# LED_PCB_Rev2.net
KiCad netlist of a schematic drawn in EAGLE
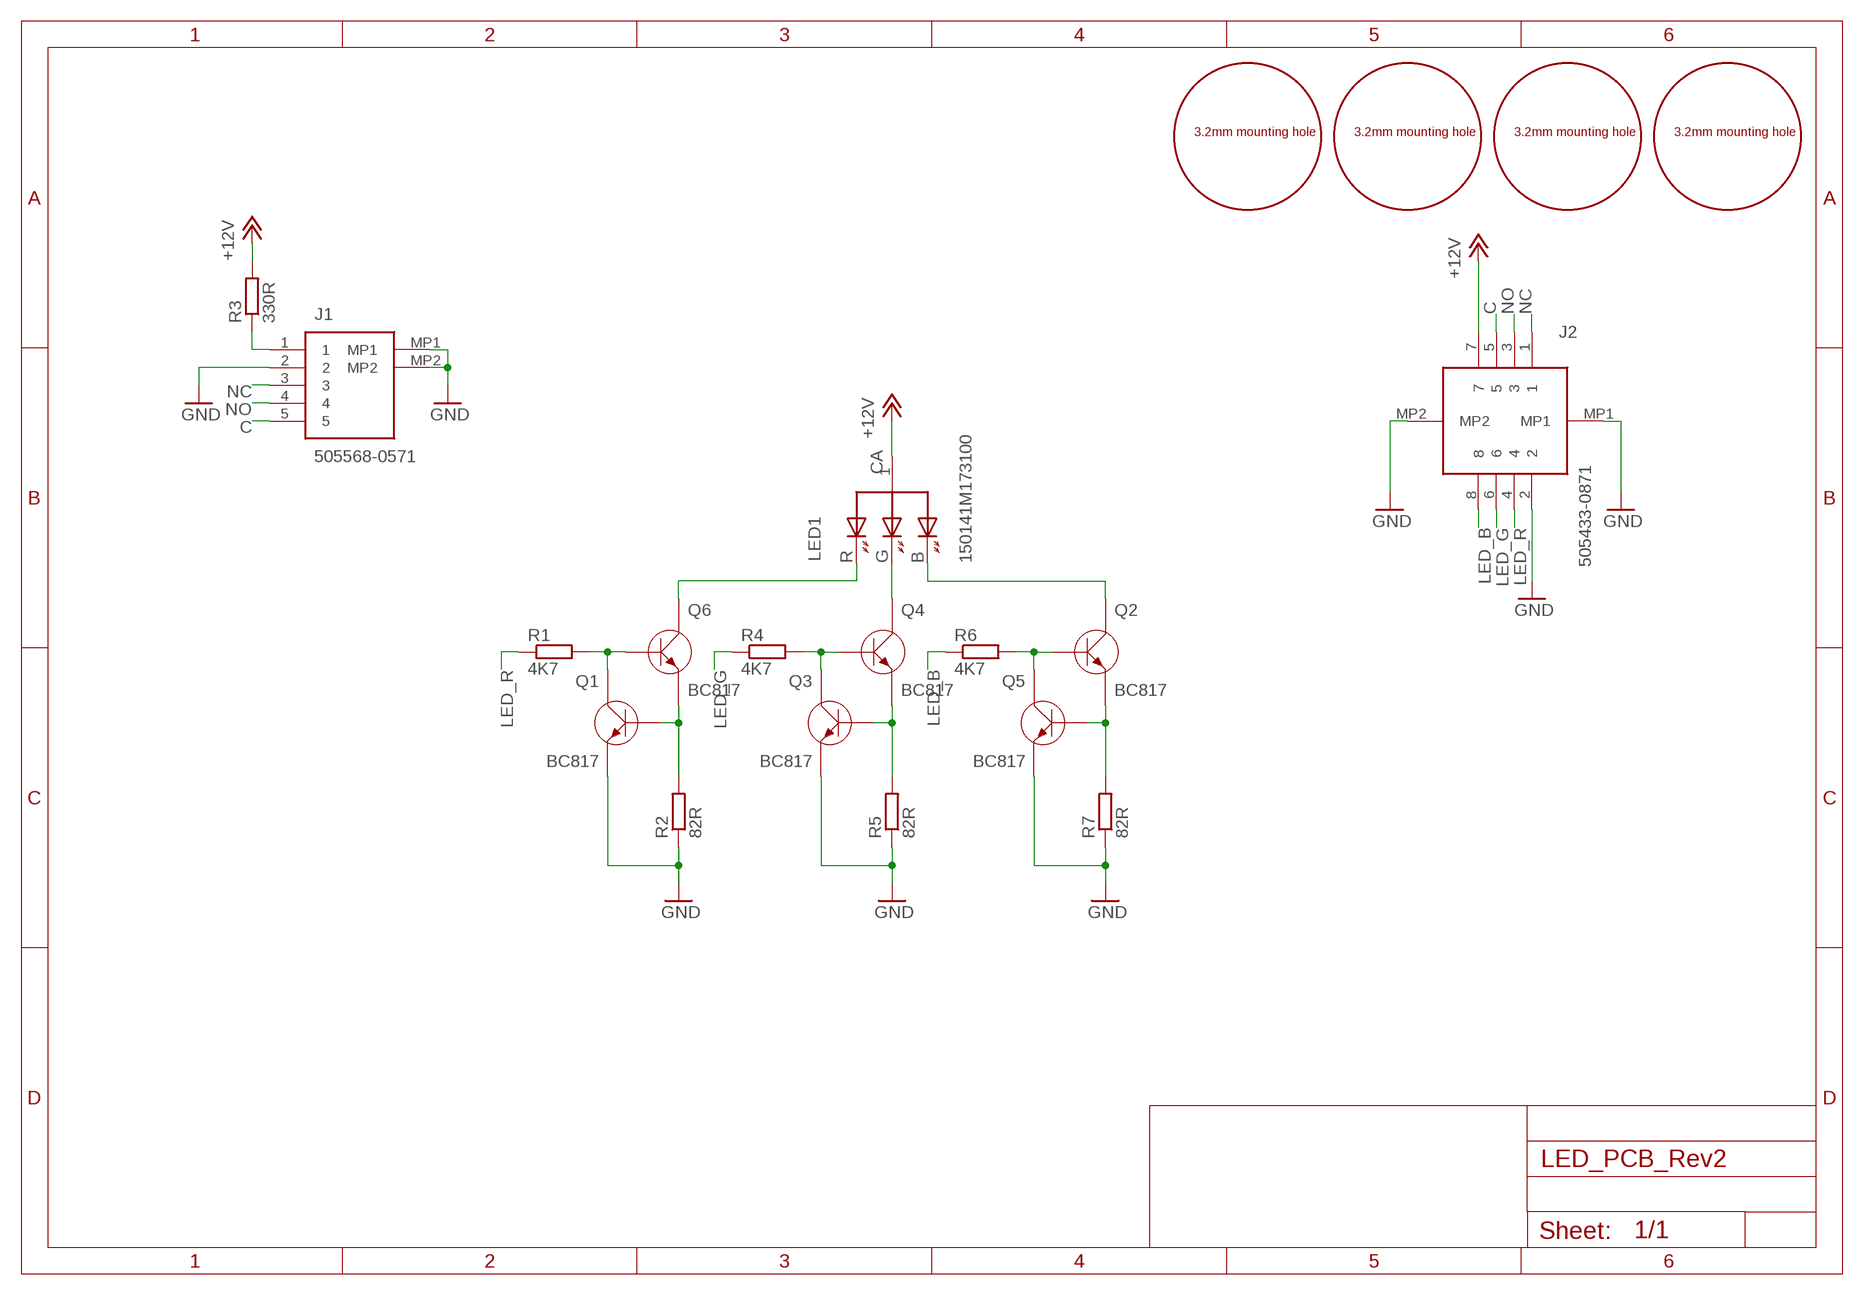
[diagram p0: schematic, sheet 1]

(export (version "E")
  (design (tool "Eeschema 10.0.6"))
  (components
    (comp (ref "J1")
      (value "505568-0571")
      (footprint "eagle-import:5055680571")
      (fields (field (name "RS_PART_NUMBER") "1615926P"))
      (libsource (lib "eagle-import") (part "505568-0571"))
    )
    (comp (ref "J2")
      (value "505433-0871")
      (footprint "eagle-import:5054330871")
      (fields (field (name "MANUFACTURER_PART_NUMBER") "5054330871"))
      (libsource (lib "eagle-import") (part "505433-0871"))
    )
    (comp (ref "LED1")
      (value "150141M173100")
      (footprint "eagle-import:150141M173100")
      (libsource (lib "eagle-import") (part "150141M173100"))
    )
    (comp (ref "Q1")
      (value "BC817")
      (footprint "eagle-import:SOT23")
      (libsource (lib "eagle-import") (part "BC817"))
    )
    (comp (ref "Q2")
      (value "BC817")
      (footprint "eagle-import:SOT23")
      (libsource (lib "eagle-import") (part "BC817"))
    )
    (comp (ref "Q3")
      (value "BC817")
      (footprint "eagle-import:SOT23")
      (libsource (lib "eagle-import") (part "BC817"))
    )
    (comp (ref "Q4")
      (value "BC817")
      (footprint "eagle-import:SOT23")
      (libsource (lib "eagle-import") (part "BC817"))
    )
    (comp (ref "Q5")
      (value "BC817")
      (footprint "eagle-import:SOT23")
      (libsource (lib "eagle-import") (part "BC817"))
    )
    (comp (ref "Q6")
      (value "BC817")
      (footprint "eagle-import:SOT23")
      (libsource (lib "eagle-import") (part "BC817"))
    )
    (comp (ref "R1")
      (value "4K7")
      (footprint "eagle-import:R0603")
      (libsource (lib "eagle-import") (part "R0603"))
    )
    (comp (ref "R2")
      (value "82R")
      (footprint "eagle-import:R0603")
      (libsource (lib "eagle-import") (part "R0603"))
    )
    (comp (ref "R3")
      (value "330R")
      (footprint "eagle-import:R0603")
      (libsource (lib "eagle-import") (part "R0603"))
    )
    (comp (ref "R4")
      (value "4K7")
      (footprint "eagle-import:R0603")
      (libsource (lib "eagle-import") (part "R0603"))
    )
    (comp (ref "R5")
      (value "82R")
      (footprint "eagle-import:R0603")
      (libsource (lib "eagle-import") (part "R0603"))
    )
    (comp (ref "R6")
      (value "4K7")
      (footprint "eagle-import:R0603")
      (libsource (lib "eagle-import") (part "R0603"))
    )
    (comp (ref "R7")
      (value "82R")
      (footprint "eagle-import:R0603")
      (libsource (lib "eagle-import") (part "R0603"))
    )
    (comp (ref "U$1")
      (value "M3_MOUNTING_HOLE")
      (footprint "eagle-import:M3_MOUNTING_HOLE")
      (libsource (lib "eagle-import") (part "M3_MOUNTING_HOLE"))
    )
    (comp (ref "U$2")
      (value "M3_MOUNTING_HOLE")
      (footprint "eagle-import:M3_MOUNTING_HOLE")
      (libsource (lib "eagle-import") (part "M3_MOUNTING_HOLE"))
    )
    (comp (ref "U$3")
      (value "M3_MOUNTING_HOLE")
      (footprint "eagle-import:M3_MOUNTING_HOLE")
      (libsource (lib "eagle-import") (part "M3_MOUNTING_HOLE"))
    )
    (comp (ref "U$4")
      (value "M3_MOUNTING_HOLE")
      (footprint "eagle-import:M3_MOUNTING_HOLE")
      (libsource (lib "eagle-import") (part "M3_MOUNTING_HOLE"))
    )
  )
  (nets
    (net (code "1") (name "+12V") (class "Default")
      (node (ref "J2") (pin "7") (pinfunction "7_7") (pintype "bidirectional"))
      (node (ref "LED1") (pin "1") (pinfunction "CA_1") (pintype "bidirectional"))
      (node (ref "R3") (pin "2") (pinfunction "2_2") (pintype "passive"))
    )
    (net (code "2") (name "/C") (class "Default")
      (node (ref "J1") (pin "5") (pinfunction "5_5") (pintype "bidirectional"))
      (node (ref "J2") (pin "5") (pinfunction "5_5") (pintype "bidirectional"))
    )
    (net (code "3") (name "/LED_B") (class "Default")
      (node (ref "J2") (pin "8") (pinfunction "8_8") (pintype "bidirectional"))
      (node (ref "R6") (pin "1") (pinfunction "1_1") (pintype "passive"))
    )
    (net (code "4") (name "/LED_G") (class "Default")
      (node (ref "J2") (pin "6") (pinfunction "6_6") (pintype "bidirectional"))
      (node (ref "R4") (pin "1") (pinfunction "1_1") (pintype "passive"))
    )
    (net (code "5") (name "/LED_R") (class "Default")
      (node (ref "J2") (pin "4") (pinfunction "4_4") (pintype "bidirectional"))
      (node (ref "R1") (pin "1") (pinfunction "1_1") (pintype "passive"))
    )
    (net (code "6") (name "/NC") (class "Default")
      (node (ref "J1") (pin "3") (pinfunction "3_3") (pintype "bidirectional"))
      (node (ref "J2") (pin "1") (pinfunction "1_1") (pintype "bidirectional"))
    )
    (net (code "7") (name "/NO") (class "Default")
      (node (ref "J1") (pin "4") (pinfunction "4_4") (pintype "bidirectional"))
      (node (ref "J2") (pin "3") (pinfunction "3_3") (pintype "bidirectional"))
    )
    (net (code "8") (name "GND") (class "Default")
      (node (ref "J1") (pin "2") (pinfunction "2_2") (pintype "bidirectional"))
      (node (ref "J1") (pin "MP1") (pinfunction "MP1_MP1") (pintype "bidirectional"))
      (node (ref "J1") (pin "MP2") (pinfunction "MP2_MP2") (pintype "bidirectional"))
      (node (ref "J2") (pin "2") (pinfunction "2_2") (pintype "bidirectional"))
      (node (ref "J2") (pin "MP1") (pinfunction "MP1_MP1") (pintype "bidirectional"))
      (node (ref "J2") (pin "MP2") (pinfunction "MP2_MP2") (pintype "bidirectional"))
      (node (ref "Q1") (pin "2") (pinfunction "E_2") (pintype "passive"))
      (node (ref "Q3") (pin "2") (pinfunction "E_2") (pintype "passive"))
      (node (ref "Q5") (pin "2") (pinfunction "E_2") (pintype "passive"))
      (node (ref "R2") (pin "1") (pinfunction "1_1") (pintype "passive"))
      (node (ref "R5") (pin "1") (pinfunction "1_1") (pintype "passive"))
      (node (ref "R7") (pin "1") (pinfunction "1_1") (pintype "passive"))
    )
    (net (code "9") (name "Net-(J1-Pad1)") (class "Default")
      (node (ref "J1") (pin "1") (pinfunction "1_1") (pintype "bidirectional"))
      (node (ref "R3") (pin "1") (pinfunction "1_1") (pintype "passive"))
    )
    (net (code "10") (name "Net-(LED1-B)") (class "Default")
      (node (ref "LED1") (pin "2") (pinfunction "B_2") (pintype "bidirectional"))
      (node (ref "Q2") (pin "3") (pinfunction "C_3") (pintype "passive"))
    )
    (net (code "11") (name "Net-(LED1-G)") (class "Default")
      (node (ref "LED1") (pin "4") (pinfunction "G_4") (pintype "bidirectional"))
      (node (ref "Q4") (pin "3") (pinfunction "C_3") (pintype "passive"))
    )
    (net (code "12") (name "Net-(LED1-R)") (class "Default")
      (node (ref "LED1") (pin "3") (pinfunction "R_3") (pintype "bidirectional"))
      (node (ref "Q6") (pin "3") (pinfunction "C_3") (pintype "passive"))
    )
    (net (code "13") (name "Net-(Q1-B)") (class "Default")
      (node (ref "Q1") (pin "1") (pinfunction "B_1") (pintype "passive"))
      (node (ref "Q6") (pin "2") (pinfunction "E_2") (pintype "passive"))
      (node (ref "R2") (pin "2") (pinfunction "2_2") (pintype "passive"))
    )
    (net (code "14") (name "Net-(Q1-C)") (class "Default")
      (node (ref "Q1") (pin "3") (pinfunction "C_3") (pintype "passive"))
      (node (ref "Q6") (pin "1") (pinfunction "B_1") (pintype "passive"))
      (node (ref "R1") (pin "2") (pinfunction "2_2") (pintype "passive"))
    )
    (net (code "15") (name "Net-(Q2-B)") (class "Default")
      (node (ref "Q2") (pin "1") (pinfunction "B_1") (pintype "passive"))
      (node (ref "Q5") (pin "3") (pinfunction "C_3") (pintype "passive"))
      (node (ref "R6") (pin "2") (pinfunction "2_2") (pintype "passive"))
    )
    (net (code "16") (name "Net-(Q2-E)") (class "Default")
      (node (ref "Q2") (pin "2") (pinfunction "E_2") (pintype "passive"))
      (node (ref "Q5") (pin "1") (pinfunction "B_1") (pintype "passive"))
      (node (ref "R7") (pin "2") (pinfunction "2_2") (pintype "passive"))
    )
    (net (code "17") (name "Net-(Q3-B)") (class "Default")
      (node (ref "Q3") (pin "1") (pinfunction "B_1") (pintype "passive"))
      (node (ref "Q4") (pin "2") (pinfunction "E_2") (pintype "passive"))
      (node (ref "R5") (pin "2") (pinfunction "2_2") (pintype "passive"))
    )
    (net (code "18") (name "Net-(Q3-C)") (class "Default")
      (node (ref "Q3") (pin "3") (pinfunction "C_3") (pintype "passive"))
      (node (ref "Q4") (pin "1") (pinfunction "B_1") (pintype "passive"))
      (node (ref "R4") (pin "2") (pinfunction "2_2") (pintype "passive"))
    )
  )
)
